# RS485.net
KiCad netlist of a schematic drawn in Altium Designer
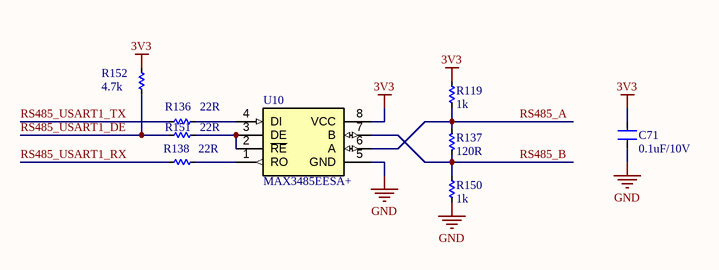
[diagram p0: RS485.SchDoc]

(export (version "E")
  (design (tool "Eeschema 10.0.6"))
  (components
    (comp (ref "C71")
      (value "0.1uF/10V")
      (footprint "CAP_C_1608X80")
      (libsource (lib "EXP_HW_V3") (part "Capacitors"))
    )
    (comp (ref "R119")
      (value "1k")
      (footprint "RES_C_1608X60")
      (description "SMD")
      (fields
        (field (name "MANUFACTURER") "Generic Components")
        (field (name "PUBLISHER") "Altium Hobart Technology Centre")
      )
      (libsource (lib "EXP_HW_V3") (part "Res SMD"))
    )
    (comp (ref "R136")
      (value "22R")
      (footprint "RES_C_1608X60")
      (description "SMD")
      (fields
        (field (name "MANUFACTURER") "Generic Components")
        (field (name "PUBLISHER") "Altium Hobart Technology Centre")
      )
      (libsource (lib "EXP_HW_V3") (part "Res SMD"))
    )
    (comp (ref "R137")
      (value "120R")
      (footprint "RES_C_1608X60")
      (description "SMD")
      (fields
        (field (name "MANUFACTURER") "Generic Components")
        (field (name "PUBLISHER") "Altium Hobart Technology Centre")
      )
      (libsource (lib "EXP_HW_V3") (part "Res SMD"))
    )
    (comp (ref "R138")
      (value "22R")
      (footprint "RES_C_1608X60")
      (description "SMD")
      (fields
        (field (name "MANUFACTURER") "Generic Components")
        (field (name "PUBLISHER") "Altium Hobart Technology Centre")
      )
      (libsource (lib "EXP_HW_V3") (part "Res SMD"))
    )
    (comp (ref "R150")
      (value "1k")
      (footprint "RES_C_1608X60")
      (description "SMD")
      (fields
        (field (name "MANUFACTURER") "Generic Components")
        (field (name "PUBLISHER") "Altium Hobart Technology Centre")
      )
      (libsource (lib "EXP_HW_V3") (part "Res SMD"))
    )
    (comp (ref "R151")
      (value "22R")
      (footprint "RES_C_1608X60")
      (description "SMD")
      (fields
        (field (name "MANUFACTURER") "Generic Components")
        (field (name "PUBLISHER") "Altium Hobart Technology Centre")
      )
      (libsource (lib "EXP_HW_V3") (part "Res SMD"))
    )
    (comp (ref "R152")
      (value "4.7k")
      (footprint "RES_C_1608X60")
      (description "SMD")
      (fields
        (field (name "MANUFACTURER") "Generic Components")
        (field (name "PUBLISHER") "Altium Hobart Technology Centre")
      )
      (libsource (lib "EXP_HW_V3") (part "Res SMD"))
    )
    (comp (ref "U10")
      (value "MAX3485EESA+")
      (footprint "SOIC8_3.9mm")
      (description "3.3V Powered, Â±15kV ESD-Protected, 12Mbps, Slew-Rate-Limited True RS-485/RS-422 Transceivers")
      (fields (field (name "MF") "Analog Devices"))
      (libsource (lib "EXP_HW_V3") (part "MAX3485EESA+"))
    )
  )
  (nets
    (net (code "1") (name "/RS485_A") (class "Default")
      (node (ref "R119") (pin "1") (pinfunction "1_1") (pintype "passive"))
      (node (ref "R137") (pin "1") (pinfunction "1_1") (pintype "passive"))
      (node (ref "U10") (pin "6") (pinfunction "A_6") (pintype "bidirectional"))
    )
    (net (code "2") (name "/RS485_B") (class "Default")
      (node (ref "R137") (pin "2") (pinfunction "2_2") (pintype "passive"))
      (node (ref "R150") (pin "2") (pinfunction "2_2") (pintype "passive"))
      (node (ref "U10") (pin "7") (pinfunction "B_7") (pintype "bidirectional"))
    )
    (net (code "3") (name "/RS485_USART1_DE") (class "Default")
      (node (ref "R151") (pin "1") (pinfunction "1_1") (pintype "passive"))
      (node (ref "R152") (pin "2") (pinfunction "2_2") (pintype "passive"))
    )
    (net (code "4") (name "/RS485_USART1_RX") (class "Default")
      (node (ref "R138") (pin "1") (pinfunction "1_1") (pintype "passive"))
    )
    (net (code "5") (name "/RS485_USART1_TX") (class "Default")
      (node (ref "R136") (pin "1") (pinfunction "1_1") (pintype "passive"))
    )
    (net (code "6") (name "3V3") (class "Default")
      (node (ref "C71") (pin "2") (pinfunction "2_2") (pintype "passive"))
      (node (ref "R119") (pin "2") (pinfunction "2_2") (pintype "passive"))
      (node (ref "R152") (pin "1") (pinfunction "1_1") (pintype "passive"))
      (node (ref "U10") (pin "8") (pinfunction "VCC_8") (pintype "power_in"))
    )
    (net (code "7") (name "GND") (class "Default")
      (node (ref "C71") (pin "1") (pinfunction "1_1") (pintype "passive"))
      (node (ref "R150") (pin "1") (pinfunction "1_1") (pintype "passive"))
      (node (ref "U10") (pin "5") (pinfunction "GND_5") (pintype "power_in"))
    )
    (net (code "8") (name "Net-(U10-DE)") (class "Default")
      (node (ref "R151") (pin "2") (pinfunction "2_2") (pintype "passive"))
      (node (ref "U10") (pin "2") (pinfunction "~{RE}_2") (pintype "passive"))
      (node (ref "U10") (pin "3") (pinfunction "DE_3") (pintype "passive"))
    )
    (net (code "9") (name "Net-(U10-DI)") (class "Default")
      (node (ref "R136") (pin "2") (pinfunction "2_2") (pintype "passive"))
      (node (ref "U10") (pin "4") (pinfunction "DI_4") (pintype "input"))
    )
    (net (code "10") (name "Net-(U10-RO)") (class "Default")
      (node (ref "R138") (pin "2") (pinfunction "2_2") (pintype "passive"))
      (node (ref "U10") (pin "1") (pinfunction "RO_1") (pintype "output"))
    )
  )
)
